# MySens-GWeasySensRS485-V03-062.net
KiCad netlist of a schematic drawn in EAGLE
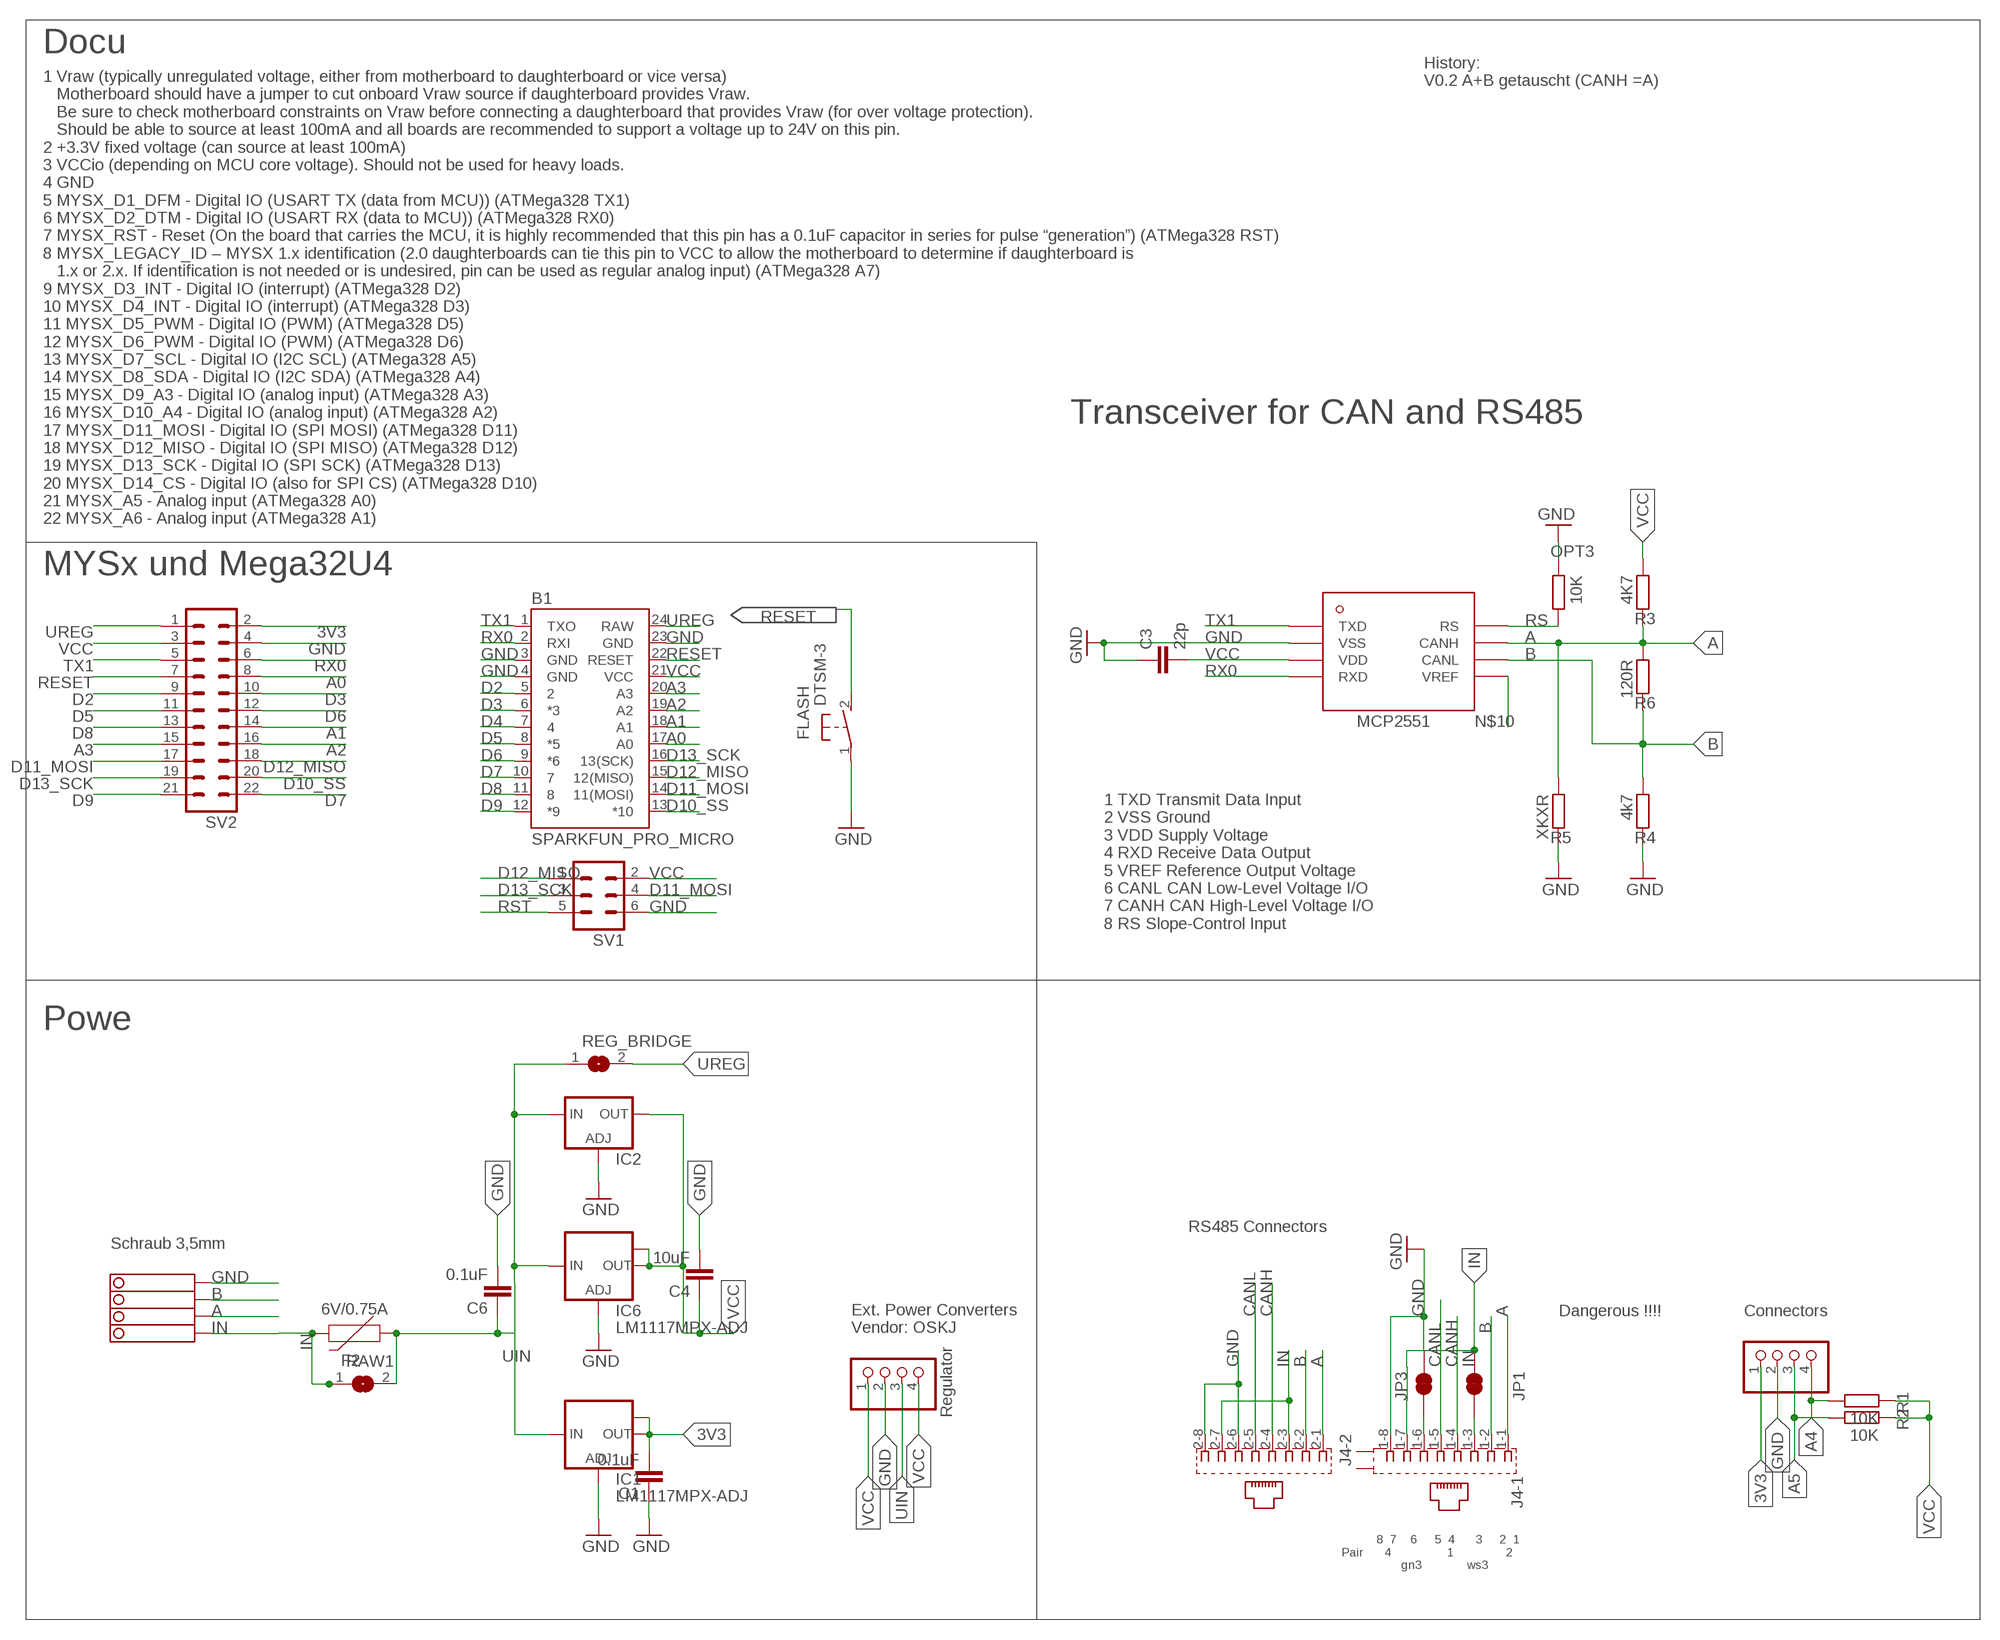
[diagram p0: schematic, sheet 1]

(export (version "E")
  (design (tool "Eeschema 10.0.6"))
  (components
    (comp (ref "B1")
      (value "SPARKFUN_PRO_MICRO")
      (footprint "eagle-import:SPARKFUN_PRO_MICRO")
      (libsource (lib "eagle-import") (part "SPARKFUN_PRO_MICRO"))
    )
    (comp (ref "C1")
      (value "0.1uF")
      (footprint "eagle-import:C1206")
      (libsource (lib "eagle-import") (part "C-EUC1206"))
    )
    (comp (ref "C3")
      (value "22p")
      (footprint "eagle-import:C0805")
      (libsource (lib "eagle-import") (part "C-EUC0805"))
    )
    (comp (ref "C4")
      (value "10uF")
      (footprint "eagle-import:C1210")
      (libsource (lib "eagle-import") (part "C-EUC1210"))
    )
    (comp (ref "C6")
      (value "0.1uF")
      (footprint "eagle-import:C1206")
      (libsource (lib "eagle-import") (part "C-EUC1206"))
    )
    (comp (ref "F2")
      (value "6V/0.75A")
      (footprint "eagle-import:1206")
      (libsource (lib "eagle-import") (part "PPTC_THREE-QUARTER-AMP"))
    )
    (comp (ref "FLASH")
      (value "DTSM-3")
      (footprint "eagle-import:DTSM-3")
      (libsource (lib "eagle-import") (part "DTSM-3"))
    )
    (comp (ref "I2C")
      (value "PINHD-1X04_2.54-S")
      (footprint "eagle-import:1X04-S")
      (libsource (lib "eagle-import") (part "PINHD-1X04_2.54-S"))
    )
    (comp (ref "IC1")
      (value "LM1117MPX-ADJ")
      (footprint "eagle-import:SOT223")
      (libsource (lib "eagle-import") (part "LM1117MPX-ADJ"))
    )
    (comp (ref "IC2")
      (value "LD117ADT50TR")
      (footprint "eagle-import:DPACK")
      (libsource (lib "eagle-import") (part "LD117A?DT50TR"))
    )
    (comp (ref "IC6")
      (value "LM1117MPX-ADJ")
      (footprint "eagle-import:SOT223")
      (libsource (lib "eagle-import") (part "LM1117MPX-ADJ"))
    )
    (comp (ref "J4")
      (value "RJ45_2X_S")
      (footprint "eagle-import:RJ45_2X_S")
      (libsource (lib "eagle-import") (part "RJ45_2X_S"))
    )
    (comp (ref "JP1")
      (value "JUMPER-SMT_2_NC_TRACE_SILK")
      (footprint "eagle-import:SMT-JUMPER_2_NC_TRACE_SILK")
      (libsource (lib "eagle-import") (part "JUMPER-SMT_2_NC_TRACE_SILK"))
    )
    (comp (ref "JP3")
      (value "JUMPER-SMT_2_NC_TRACE_SILK")
      (footprint "eagle-import:SMT-JUMPER_2_NC_TRACE_SILK")
      (libsource (lib "eagle-import") (part "JUMPER-SMT_2_NC_TRACE_SILK"))
    )
    (comp (ref "OPT3")
      (value "10K")
      (footprint "eagle-import:R0805")
      (libsource (lib "eagle-import") (part "R-EU_R0805"))
    )
    (comp (ref "R1")
      (value "10K")
      (footprint "eagle-import:R0805")
      (libsource (lib "eagle-import") (part "R-EU_R0805"))
    )
    (comp (ref "R2")
      (value "10K")
      (footprint "eagle-import:R0805")
      (libsource (lib "eagle-import") (part "R-EU_R0805"))
    )
    (comp (ref "R3")
      (value "4K7")
      (footprint "eagle-import:R0805")
      (libsource (lib "eagle-import") (part "R-EU_R0805"))
    )
    (comp (ref "R4")
      (value "4k7")
      (footprint "eagle-import:R0805")
      (libsource (lib "eagle-import") (part "R-EU_R0805"))
    )
    (comp (ref "R5")
      (value "XKXR")
      (footprint "eagle-import:R0805")
      (libsource (lib "eagle-import") (part "R-EU_R0805"))
    )
    (comp (ref "R6")
      (value "120R")
      (footprint "eagle-import:R0805")
      (libsource (lib "eagle-import") (part "R-EU_R0805"))
    )
    (comp (ref "RAW1")
      (value "SJ")
      (footprint "eagle-import:SJ")
      (libsource (lib "eagle-import") (part "SJ"))
    )
    (comp (ref "REG_BRIDGE")
      (value "SJ")
      (footprint "eagle-import:SJ")
      (libsource (lib "eagle-import") (part "SJ"))
    )
    (comp (ref "STEPDWN")
      (value "PINHD-1X04_2.54-S")
      (footprint "eagle-import:1X04-S")
      (libsource (lib "eagle-import") (part "PINHD-1X04_2.54-S"))
    )
    (comp (ref "SV1")
      (value "MA03-2")
      (footprint "eagle-import:MA03-2")
      (libsource (lib "eagle-import") (part "MA03-2"))
    )
    (comp (ref "SV2")
      (value "MA11-2")
      (footprint "eagle-import:MA11-2")
      (libsource (lib "eagle-import") (part "MA11-2"))
    )
    (comp (ref "U$1")
      (value "MCP2551")
      (footprint "eagle-import:SOIC-8")
      (libsource (lib "eagle-import") (part "MCP2551"))
    )
    (comp (ref "X4")
      (value "1751264")
      (footprint "eagle-import:1751264")
      (libsource (lib "eagle-import") (part "1751264"))
    )
  )
  (nets
    (net (code "1") (name "/A0") (class "Default")
      (node (ref "B1") (pin "17") (pinfunction "A0_17") (pintype "bidirectional"))
      (node (ref "SV2") (pin "8") (pinfunction "8_8") (pintype "passive"))
    )
    (net (code "2") (name "/A1") (class "Default")
      (node (ref "B1") (pin "18") (pinfunction "A1_18") (pintype "bidirectional"))
      (node (ref "SV2") (pin "14") (pinfunction "14_14") (pintype "passive"))
    )
    (net (code "3") (name "/A2") (class "Default")
      (node (ref "B1") (pin "19") (pinfunction "A2_19") (pintype "bidirectional"))
      (node (ref "SV2") (pin "16") (pinfunction "16_16") (pintype "passive"))
    )
    (net (code "4") (name "/A3") (class "Default")
      (node (ref "B1") (pin "20") (pinfunction "A3_20") (pintype "bidirectional"))
      (node (ref "SV2") (pin "15") (pinfunction "15_15") (pintype "passive"))
    )
    (net (code "5") (name "/CANH") (class "Default")
      (node (ref "J4") (pin "1-4") (pinfunction "4_1-4") (pintype "passive"))
      (node (ref "J4") (pin "2-4") (pinfunction "4_2-4") (pintype "passive"))
    )
    (net (code "6") (name "/CANL") (class "Default")
      (node (ref "J4") (pin "1-5") (pinfunction "5_1-5") (pintype "passive"))
      (node (ref "J4") (pin "2-5") (pinfunction "5_2-5") (pintype "passive"))
    )
    (net (code "7") (name "/D2") (class "Default")
      (node (ref "B1") (pin "5") (pinfunction "2_5") (pintype "bidirectional"))
      (node (ref "SV2") (pin "9") (pinfunction "9_9") (pintype "passive"))
    )
    (net (code "8") (name "/D3") (class "Default")
      (node (ref "B1") (pin "6") (pinfunction "*3_6") (pintype "bidirectional"))
      (node (ref "SV2") (pin "10") (pinfunction "10_10") (pintype "passive"))
    )
    (net (code "9") (name "/D4") (class "Default")
      (node (ref "B1") (pin "7") (pinfunction "4_7") (pintype "bidirectional"))
    )
    (net (code "10") (name "/D5") (class "Default")
      (node (ref "B1") (pin "8") (pinfunction "*5_8") (pintype "bidirectional"))
      (node (ref "SV2") (pin "11") (pinfunction "11_11") (pintype "passive"))
    )
    (net (code "11") (name "/D6") (class "Default")
      (node (ref "B1") (pin "9") (pinfunction "*6_9") (pintype "bidirectional"))
      (node (ref "SV2") (pin "12") (pinfunction "12_12") (pintype "passive"))
    )
    (net (code "12") (name "/D7") (class "Default")
      (node (ref "B1") (pin "10") (pinfunction "7_10") (pintype "bidirectional"))
      (node (ref "SV2") (pin "22") (pinfunction "22_22") (pintype "passive"))
    )
    (net (code "13") (name "/D8") (class "Default")
      (node (ref "B1") (pin "11") (pinfunction "8_11") (pintype "bidirectional"))
      (node (ref "SV2") (pin "13") (pinfunction "13_13") (pintype "passive"))
    )
    (net (code "14") (name "/D9") (class "Default")
      (node (ref "B1") (pin "12") (pinfunction "*9_12") (pintype "bidirectional"))
      (node (ref "SV2") (pin "21") (pinfunction "21_21") (pintype "passive"))
    )
    (net (code "15") (name "/D10_SS") (class "Default")
      (node (ref "B1") (pin "13") (pinfunction "*10_13") (pintype "bidirectional"))
      (node (ref "SV2") (pin "20") (pinfunction "20_20") (pintype "passive"))
    )
    (net (code "16") (name "/D11_MOSI") (class "Default")
      (node (ref "B1") (pin "14") (pinfunction "11(MOSI)_14") (pintype "bidirectional"))
      (node (ref "SV1") (pin "4") (pinfunction "4_4") (pintype "passive"))
      (node (ref "SV2") (pin "17") (pinfunction "17_17") (pintype "passive"))
    )
    (net (code "17") (name "/D12_MISO") (class "Default")
      (node (ref "B1") (pin "15") (pinfunction "12(MISO)_15") (pintype "bidirectional"))
      (node (ref "SV1") (pin "1") (pinfunction "1_1") (pintype "passive"))
      (node (ref "SV2") (pin "18") (pinfunction "18_18") (pintype "passive"))
    )
    (net (code "18") (name "/D13_SCK") (class "Default")
      (node (ref "B1") (pin "16") (pinfunction "13(SCK)_16") (pintype "bidirectional"))
      (node (ref "SV1") (pin "3") (pinfunction "3_3") (pintype "passive"))
      (node (ref "SV2") (pin "19") (pinfunction "19_19") (pintype "passive"))
    )
    (net (code "19") (name "/N$10") (class "Default")
      (node (ref "U$1") (pin "VREF") (pinfunction "VREF_VREF") (pintype "bidirectional"))
    )
    (net (code "20") (name "/RESET") (class "Default")
      (node (ref "B1") (pin "22") (pinfunction "RESET_22") (pintype "bidirectional"))
      (node (ref "FLASH") (pin "2") (pinfunction "2_2") (pintype "passive"))
      (node (ref "SV2") (pin "7") (pinfunction "7_7") (pintype "passive"))
    )
    (net (code "21") (name "/RS") (class "Default")
      (node (ref "OPT3") (pin "2") (pinfunction "2_2") (pintype "passive"))
      (node (ref "U$1") (pin "RS") (pinfunction "RS_RS") (pintype "bidirectional"))
    )
    (net (code "22") (name "/RST") (class "Default")
      (node (ref "SV1") (pin "5") (pinfunction "5_5") (pintype "passive"))
    )
    (net (code "23") (name "/RX0") (class "Default")
      (node (ref "B1") (pin "2") (pinfunction "RXI_2") (pintype "bidirectional"))
      (node (ref "SV2") (pin "6") (pinfunction "6_6") (pintype "passive"))
      (node (ref "U$1") (pin "RXD") (pinfunction "RXD_RXD") (pintype "bidirectional"))
    )
    (net (code "24") (name "/TX1") (class "Default")
      (node (ref "B1") (pin "1") (pinfunction "TXO_1") (pintype "bidirectional"))
      (node (ref "SV2") (pin "5") (pinfunction "5_5") (pintype "passive"))
      (node (ref "U$1") (pin "TXD") (pinfunction "TXD_TXD") (pintype "bidirectional"))
    )
    (net (code "25") (name "3V3") (class "Default")
      (node (ref "C1") (pin "2") (pinfunction "2_2") (pintype "passive"))
      (node (ref "I2C") (pin "1") (pinfunction "1_1") (pintype "passive"))
      (node (ref "IC1") (pin "2") (pinfunction "OUT_2") (pintype "passive"))
      (node (ref "IC1") (pin "TAB") (pinfunction "OUT1_TAB") (pintype "passive"))
      (node (ref "SV2") (pin "2") (pinfunction "2_2") (pintype "passive"))
    )
    (net (code "26") (name "A") (class "Default")
      (node (ref "J4") (pin "1-1") (pinfunction "1_1-1") (pintype "passive"))
      (node (ref "J4") (pin "2-1") (pinfunction "1_2-1") (pintype "passive"))
      (node (ref "R3") (pin "2") (pinfunction "2_2") (pintype "passive"))
      (node (ref "R5") (pin "1") (pinfunction "1_1") (pintype "passive"))
      (node (ref "R6") (pin "1") (pinfunction "1_1") (pintype "passive"))
      (node (ref "U$1") (pin "CANH") (pinfunction "CANH_CANH") (pintype "bidirectional"))
      (node (ref "X4") (pin "2") (pinfunction "K_2") (pintype "passive"))
    )
    (net (code "27") (name "A4") (class "Default")
      (node (ref "I2C") (pin "4") (pinfunction "4_4") (pintype "passive"))
      (node (ref "R1") (pin "2") (pinfunction "2_2") (pintype "passive"))
    )
    (net (code "28") (name "A5") (class "Default")
      (node (ref "I2C") (pin "3") (pinfunction "3_3") (pintype "passive"))
      (node (ref "R2") (pin "2") (pinfunction "2_2") (pintype "passive"))
    )
    (net (code "29") (name "B") (class "Default")
      (node (ref "J4") (pin "1-2") (pinfunction "2_1-2") (pintype "passive"))
      (node (ref "J4") (pin "2-2") (pinfunction "2_2-2") (pintype "passive"))
      (node (ref "R4") (pin "1") (pinfunction "1_1") (pintype "passive"))
      (node (ref "R6") (pin "2") (pinfunction "2_2") (pintype "passive"))
      (node (ref "U$1") (pin "CANL") (pinfunction "CANL_CANL") (pintype "bidirectional"))
      (node (ref "X4") (pin "3") (pinfunction "K_3") (pintype "passive"))
    )
    (net (code "30") (name "GND") (class "Default")
      (node (ref "B1") (pin "23") (pinfunction "GND_23") (pintype "power_in"))
      (node (ref "B1") (pin "3") (pinfunction "GND_3") (pintype "power_in"))
      (node (ref "B1") (pin "4") (pinfunction "GND_4") (pintype "power_in"))
      (node (ref "C1") (pin "1") (pinfunction "1_1") (pintype "passive"))
      (node (ref "C3") (pin "1") (pinfunction "1_1") (pintype "passive"))
      (node (ref "C4") (pin "2") (pinfunction "2_2") (pintype "passive"))
      (node (ref "C6") (pin "2") (pinfunction "2_2") (pintype "passive"))
      (node (ref "FLASH") (pin "1") (pinfunction "1_1") (pintype "passive"))
      (node (ref "I2C") (pin "2") (pinfunction "2_2") (pintype "passive"))
      (node (ref "IC1") (pin "1") (pinfunction "ADJ_1") (pintype "input"))
      (node (ref "IC2") (pin "1") (pinfunction "ADJ_1") (pintype "input"))
      (node (ref "IC6") (pin "1") (pinfunction "ADJ_1") (pintype "input"))
      (node (ref "J4") (pin "1-8") (pinfunction "8_1-8") (pintype "passive"))
      (node (ref "J4") (pin "2-6") (pinfunction "6_2-6") (pintype "passive"))
      (node (ref "J4") (pin "2-8") (pinfunction "8_2-8") (pintype "passive"))
      (node (ref "JP3") (pin "2") (pinfunction "2_2") (pintype "passive"))
      (node (ref "OPT3") (pin "1") (pinfunction "1_1") (pintype "passive"))
      (node (ref "R4") (pin "2") (pinfunction "2_2") (pintype "passive"))
      (node (ref "R5") (pin "2") (pinfunction "2_2") (pintype "passive"))
      (node (ref "STEPDWN") (pin "2") (pinfunction "2_2") (pintype "passive"))
      (node (ref "SV1") (pin "6") (pinfunction "6_6") (pintype "passive"))
      (node (ref "SV2") (pin "4") (pinfunction "4_4") (pintype "passive"))
      (node (ref "U$1") (pin "VSS") (pinfunction "VSS_VSS") (pintype "bidirectional"))
      (node (ref "X4") (pin "4") (pinfunction "K_4") (pintype "passive"))
    )
    (net (code "31") (name "IN") (class "Default")
      (node (ref "F2") (pin "2") (pinfunction "2_2") (pintype "bidirectional"))
      (node (ref "J4") (pin "1-7") (pinfunction "7_1-7") (pintype "passive"))
      (node (ref "J4") (pin "2-3") (pinfunction "3_2-3") (pintype "passive"))
      (node (ref "J4") (pin "2-7") (pinfunction "7_2-7") (pintype "passive"))
      (node (ref "JP1") (pin "2") (pinfunction "2_2") (pintype "passive"))
      (node (ref "RAW1") (pin "1") (pinfunction "1_1") (pintype "passive"))
      (node (ref "X4") (pin "1") (pinfunction "K_1") (pintype "passive"))
    )
    (net (code "32") (name "Net-(J4A-3)") (class "Default")
      (node (ref "J4") (pin "1-3") (pinfunction "3_1-3") (pintype "passive"))
      (node (ref "JP1") (pin "1") (pinfunction "1_1") (pintype "passive"))
    )
    (net (code "33") (name "Net-(J4A-6)") (class "Default")
      (node (ref "J4") (pin "1-6") (pinfunction "6_1-6") (pintype "passive"))
      (node (ref "JP3") (pin "1") (pinfunction "1_1") (pintype "passive"))
    )
    (net (code "34") (name "UIN") (class "Default")
      (node (ref "C6") (pin "1") (pinfunction "1_1") (pintype "passive"))
      (node (ref "F2") (pin "1") (pinfunction "1_1") (pintype "bidirectional"))
      (node (ref "IC1") (pin "3") (pinfunction "IN_3") (pintype "input"))
      (node (ref "IC2") (pin "3") (pinfunction "IN_3") (pintype "input"))
      (node (ref "IC6") (pin "3") (pinfunction "IN_3") (pintype "input"))
      (node (ref "RAW1") (pin "2") (pinfunction "2_2") (pintype "passive"))
      (node (ref "REG_BRIDGE") (pin "1") (pinfunction "1_1") (pintype "passive"))
      (node (ref "STEPDWN") (pin "3") (pinfunction "3_3") (pintype "passive"))
    )
    (net (code "35") (name "UREG") (class "Default")
      (node (ref "B1") (pin "24") (pinfunction "RAW_24") (pintype "power_in"))
      (node (ref "REG_BRIDGE") (pin "2") (pinfunction "2_2") (pintype "passive"))
      (node (ref "SV2") (pin "1") (pinfunction "1_1") (pintype "passive"))
    )
    (net (code "36") (name "VCC") (class "Default")
      (node (ref "B1") (pin "21") (pinfunction "VCC_21") (pintype "power_in"))
      (node (ref "C3") (pin "2") (pinfunction "2_2") (pintype "passive"))
      (node (ref "C4") (pin "1") (pinfunction "1_1") (pintype "passive"))
      (node (ref "IC2") (pin "4") (pinfunction "OUT_4") (pintype "passive"))
      (node (ref "IC6") (pin "2") (pinfunction "OUT_2") (pintype "passive"))
      (node (ref "IC6") (pin "TAB") (pinfunction "OUT1_TAB") (pintype "passive"))
      (node (ref "R1") (pin "1") (pinfunction "1_1") (pintype "passive"))
      (node (ref "R2") (pin "1") (pinfunction "1_1") (pintype "passive"))
      (node (ref "R3") (pin "1") (pinfunction "1_1") (pintype "passive"))
      (node (ref "STEPDWN") (pin "1") (pinfunction "1_1") (pintype "passive"))
      (node (ref "STEPDWN") (pin "4") (pinfunction "4_4") (pintype "passive"))
      (node (ref "SV1") (pin "2") (pinfunction "2_2") (pintype "passive"))
      (node (ref "SV2") (pin "3") (pinfunction "3_3") (pintype "passive"))
      (node (ref "U$1") (pin "VDD") (pinfunction "VDD_VDD") (pintype "bidirectional"))
    )
    (net (code "37") (name "unconnected-(J4A-S1-PadG3)") (class "Default")
      (node (ref "J4") (pin "G3") (pinfunction "S1_G3") (pintype "passive"))
    )
    (net (code "38") (name "unconnected-(J4A-S2-PadG1)") (class "Default")
      (node (ref "J4") (pin "G1") (pinfunction "S2_G1") (pintype "passive"))
    )
  )
)
